# Kajtu_-DSP_processor.net
KiCad netlist of a schematic drawn in Altium Designer
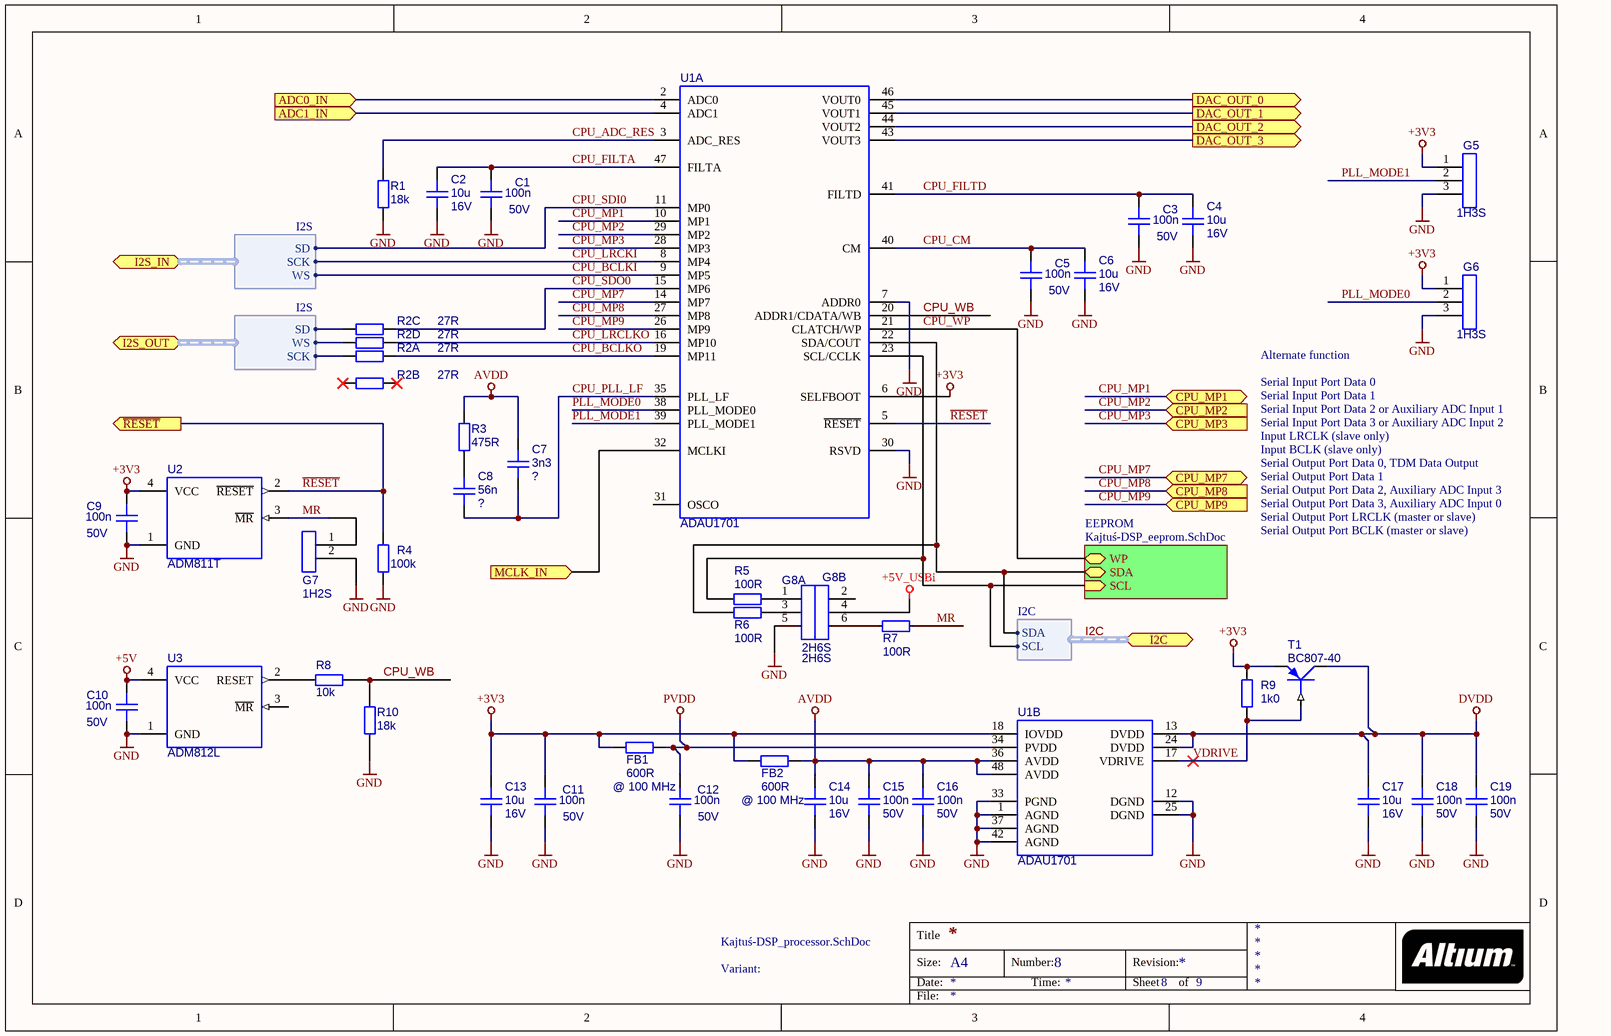
[diagram p0: Kajtuś-DSP_processor.SchDoc]

(export (version "E")
  (design (tool "Eeschema 10.0.6"))
  (components
    (comp (ref "C1")
      (value "100n")
      (footprint "C_0603_MA")
      (description "Kondensator ceramiczny SMD")
      (fields (field (name "PART NUMBER") "C_0603_100n_50V_X7R") (field (name "VOLTAGE") "50V"))
      (libsource (lib "AD_ostry_intlib") (part "C_0603_100n_50V_X7R"))
    )
    (comp (ref "C2")
      (value "10u")
      (footprint "C_0805_MA")
      (description "Kondensator ceramiczny SMD")
      (fields (field (name "PART NUMBER") "C_0805_10u_16V_X5R") (field (name "VOLTAGE") "16V"))
      (libsource (lib "AD_ostry_intlib") (part "C_0805_10u_16V_X5R"))
    )
    (comp (ref "C3")
      (value "100n")
      (footprint "C_0603_MA")
      (description "Kondensator ceramiczny SMD")
      (fields (field (name "PART NUMBER") "C_0603_100n_50V_X7R") (field (name "VOLTAGE") "50V"))
      (libsource (lib "AD_ostry_intlib") (part "C_0603_100n_50V_X7R"))
    )
    (comp (ref "C4")
      (value "10u")
      (footprint "C_0805_MA")
      (description "Kondensator ceramiczny SMD")
      (fields (field (name "PART NUMBER") "C_0805_10u_16V_X5R") (field (name "VOLTAGE") "16V"))
      (libsource (lib "AD_ostry_intlib") (part "C_0805_10u_16V_X5R"))
    )
    (comp (ref "C5")
      (value "100n")
      (footprint "C_0603_MA")
      (description "Kondensator ceramiczny SMD")
      (fields (field (name "PART NUMBER") "C_0603_100n_50V_X7R") (field (name "VOLTAGE") "50V"))
      (libsource (lib "AD_ostry_intlib") (part "C_0603_100n_50V_X7R"))
    )
    (comp (ref "C6")
      (value "10u")
      (footprint "C_0805_MA")
      (description "Kondensator ceramiczny SMD")
      (fields (field (name "PART NUMBER") "C_0805_10u_16V_X5R") (field (name "VOLTAGE") "16V"))
      (libsource (lib "AD_ostry_intlib") (part "C_0805_10u_16V_X5R"))
    )
    (comp (ref "C7")
      (value "3n3")
      (footprint "C_0603_MA")
      (description "Kondensator ceramiczny SMD")
      (fields (field (name "PART NUMBER") "C_SMD_MLCC_generic") (field (name "VOLTAGE") "?"))
      (libsource (lib "AD_ostry_intlib") (part "C_SMD_MLCC_generic"))
    )
    (comp (ref "C8")
      (value "56n")
      (footprint "C_0603_MA")
      (description "Kondensator ceramiczny SMD")
      (fields (field (name "PART NUMBER") "C_SMD_MLCC_generic") (field (name "VOLTAGE") "?"))
      (libsource (lib "AD_ostry_intlib") (part "C_SMD_MLCC_generic"))
    )
    (comp (ref "C9")
      (value "100n")
      (footprint "C_0603_MA")
      (description "Kondensator ceramiczny SMD")
      (fields (field (name "PART NUMBER") "C_0603_100n_50V_X7R") (field (name "VOLTAGE") "50V"))
      (libsource (lib "AD_ostry_intlib") (part "C_0603_100n_50V_X7R"))
    )
    (comp (ref "C10")
      (value "100n")
      (footprint "C_0603_MA")
      (description "Kondensator ceramiczny SMD")
      (fields (field (name "PART NUMBER") "C_0603_100n_50V_X7R") (field (name "VOLTAGE") "50V"))
      (libsource (lib "AD_ostry_intlib") (part "C_0603_100n_50V_X7R"))
    )
    (comp (ref "C11")
      (value "100n")
      (footprint "C_0603_MA")
      (description "Kondensator ceramiczny SMD")
      (fields (field (name "PART NUMBER") "C_0603_100n_50V_X7R") (field (name "VOLTAGE") "50V"))
      (libsource (lib "AD_ostry_intlib") (part "C_0603_100n_50V_X7R"))
    )
    (comp (ref "C12")
      (value "100n")
      (footprint "C_0603_MA")
      (description "Kondensator ceramiczny SMD")
      (fields (field (name "PART NUMBER") "C_0603_100n_50V_X7R") (field (name "VOLTAGE") "50V"))
      (libsource (lib "AD_ostry_intlib") (part "C_0603_100n_50V_X7R"))
    )
    (comp (ref "C13")
      (value "10u")
      (footprint "C_0805_MA")
      (description "Kondensator ceramiczny SMD")
      (fields (field (name "PART NUMBER") "C_0805_10u_16V_X5R") (field (name "VOLTAGE") "16V"))
      (libsource (lib "AD_ostry_intlib") (part "C_0805_10u_16V_X5R"))
    )
    (comp (ref "C14")
      (value "10u")
      (footprint "C_0805_MA")
      (description "Kondensator ceramiczny SMD")
      (fields (field (name "PART NUMBER") "C_0805_10u_16V_X5R") (field (name "VOLTAGE") "16V"))
      (libsource (lib "AD_ostry_intlib") (part "C_0805_10u_16V_X5R"))
    )
    (comp (ref "C15")
      (value "100n")
      (footprint "C_0603_MA")
      (description "Kondensator ceramiczny SMD")
      (fields (field (name "PART NUMBER") "C_0603_100n_50V_X7R") (field (name "VOLTAGE") "50V"))
      (libsource (lib "AD_ostry_intlib") (part "C_0603_100n_50V_X7R"))
    )
    (comp (ref "C16")
      (value "100n")
      (footprint "C_0603_MA")
      (description "Kondensator ceramiczny SMD")
      (fields (field (name "PART NUMBER") "C_0603_100n_50V_X7R") (field (name "VOLTAGE") "50V"))
      (libsource (lib "AD_ostry_intlib") (part "C_0603_100n_50V_X7R"))
    )
    (comp (ref "C17")
      (value "10u")
      (footprint "C_0805_MA")
      (description "Kondensator ceramiczny SMD")
      (fields (field (name "PART NUMBER") "C_0805_10u_16V_X5R") (field (name "VOLTAGE") "16V"))
      (libsource (lib "AD_ostry_intlib") (part "C_0805_10u_16V_X5R"))
    )
    (comp (ref "C18")
      (value "100n")
      (footprint "C_0603_MA")
      (description "Kondensator ceramiczny SMD")
      (fields (field (name "PART NUMBER") "C_0603_100n_50V_X7R") (field (name "VOLTAGE") "50V"))
      (libsource (lib "AD_ostry_intlib") (part "C_0603_100n_50V_X7R"))
    )
    (comp (ref "C19")
      (value "100n")
      (footprint "C_0603_MA")
      (description "Kondensator ceramiczny SMD")
      (fields (field (name "PART NUMBER") "C_0603_100n_50V_X7R") (field (name "VOLTAGE") "50V"))
      (libsource (lib "AD_ostry_intlib") (part "C_0603_100n_50V_X7R"))
    )
    (comp (ref "FB1")
      (value "600R")
      (footprint "R_0603_MA")
      (description "Koralik ferrytowy")
      (fields
        (field (name "MANUFACTURER") "Yageo")
        (field (name "PART NUMBER") "FB_0603_PBY160808T-601Y_600R_1A")
        (field (name "@ FREQUENCY") "@ 100 MHz")
      )
      (libsource (lib "AD_ostry_intlib") (part "FB_0603_PBY160808T-601Y_600R_1A"))
    )
    (comp (ref "FB2")
      (value "600R")
      (footprint "R_0603_MA")
      (description "Koralik ferrytowy")
      (fields
        (field (name "MANUFACTURER") "Yageo")
        (field (name "PART NUMBER") "FB_0603_PBY160808T-601Y_600R_1A")
        (field (name "@ FREQUENCY") "@ 100 MHz")
      )
      (libsource (lib "AD_ostry_intlib") (part "FB_0603_PBY160808T-601Y_600R_1A"))
    )
    (comp (ref "G5")
      (value "1H3S")
      (footprint "1H3S_FHS")
      (description "Listwa jednorzędowa, 1x3 piny, raster 2,54mm")
      (fields (field (name "PART NUMBER") "G_1H3S") (field (name "MANUFACTURER") "generic"))
      (libsource (lib "AD_ostry_intlib") (part "G_1H3S"))
    )
    (comp (ref "G6")
      (value "1H3S")
      (footprint "1H3S_FHS")
      (description "Listwa jednorzędowa, 1x3 piny, raster 2,54mm")
      (fields (field (name "PART NUMBER") "G_1H3S") (field (name "MANUFACTURER") "generic"))
      (libsource (lib "AD_ostry_intlib") (part "G_1H3S"))
    )
    (comp (ref "G7")
      (value "1H2S")
      (footprint "1H2S_FHS")
      (description "Listwa jednorzędowa, 1x2 piny, raster 2,54mm")
      (fields (field (name "PART NUMBER") "G_1H2S") (field (name "MANUFACTURER") "generic"))
      (libsource (lib "AD_ostry_intlib") (part "G_1H2S"))
    )
    (comp (ref "G8")
      (value "2H6S")
      (footprint "2H6S")
      (description "Listwa kołkowa")
      (fields (field (name "PART NUMBER") "G_2H6S") (field (name "MANUFACTURER") "Ninigi"))
      (libsource (lib "") (part "G_2H6S_1"))
    )
    (comp (ref "R1")
      (value "18k")
      (footprint "R_1206_MA")
      (description "SMD resistor")
      (fields (field (name "PART NUMBER") "?"))
      (libsource (lib "AD_ostry_intlib") (part "R_SMD_generic"))
    )
    (comp (ref "R2")
      (value "27R")
      (footprint "RA_1206")
      (description "SMD Resistor Array, 1206, 4x27R, 5%, 62.5mW")
      (fields (field (name "TOLERANCE") "5%"))
      (libsource (lib "AD_ostry_intlib") (part "RA_1206_4x27R_5%"))
    )
    (comp (ref "R3")
      (value "475R")
      (footprint "R_0603_MA")
      (description "SMD resistor")
      (fields (field (name "PART NUMBER") "?"))
      (libsource (lib "AD_ostry_intlib") (part "R_SMD_generic"))
    )
    (comp (ref "R4")
      (value "100k")
      (footprint "R_0603_MA")
      (description "Rezystor SMD")
      (fields (field (name "MANUFACTURER") "Royal Ohm") (field (name "PART NUMBER") "R_0603_100k_5%"))
      (libsource (lib "AD_ostry_intlib") (part "R_0603_100k_5%"))
    )
    (comp (ref "R5")
      (value "100R")
      (footprint "R_0603_MA")
      (description "Rezystor SMD")
      (fields (field (name "PART NUMBER") "R_0603_100R_5%") (field (name "MANUFACTURER") "Royal Ohm"))
      (libsource (lib "AD_ostry_intlib") (part "R_0603_100R_5%"))
    )
    (comp (ref "R6")
      (value "100R")
      (footprint "R_0603_MA")
      (description "Rezystor SMD")
      (fields (field (name "PART NUMBER") "R_0603_100R_5%") (field (name "MANUFACTURER") "Royal Ohm"))
      (libsource (lib "AD_ostry_intlib") (part "R_0603_100R_5%"))
    )
    (comp (ref "R7")
      (value "100R")
      (footprint "R_0603_MA")
      (description "Rezystor SMD")
      (fields (field (name "PART NUMBER") "R_0603_100R_5%") (field (name "MANUFACTURER") "Royal Ohm"))
      (libsource (lib "AD_ostry_intlib") (part "R_0603_100R_5%"))
    )
    (comp (ref "R8")
      (value "10k")
      (footprint "R_0603_MA")
      (description "Rezystor SMD")
      (fields (field (name "MANUFACTURER") "Royal Ohm") (field (name "PART NUMBER") "R_0603_10k_5%"))
      (libsource (lib "AD_ostry_intlib") (part "R_0603_10k_5%"))
    )
    (comp (ref "R9")
      (value "1k0")
      (footprint "R_0603_MA")
      (description "Rezystor SMD")
      (fields (field (name "MANUFACTURER") "Royal Ohm") (field (name "PART NUMBER") "R_0603_1k0_5%"))
      (libsource (lib "AD_ostry_intlib") (part "R_0603_1k0_5%"))
    )
    (comp (ref "R10")
      (value "18k")
      (footprint "R_0603_MA")
      (description "SMD resistor")
      (fields (field (name "PART NUMBER") "?"))
      (libsource (lib "AD_ostry_intlib") (part "R_SMD_generic"))
    )
    (comp (ref "T1")
      (value "BC807-40")
      (footprint "SOT-23")
      (description "Tranzystor bipolarny PNP")
      (fields (field (name "PART NUMBER") "T_SOT-23_BC807-40") (field (name "MANUFACTURER") "NXP"))
      (libsource (lib "AD_ostry_intlib") (part "T_SOT-23_BC807-40"))
    )
    (comp (ref "U1")
      (value "ADAU1701")
      (footprint "TSQFP50P900X900X160-48N")
      (description "SigmaDSP 28-/56-Bit Audio Processor with Two ADCs and Four DACs")
      (fields (field (name "MANUFACTURER") "Analog Devices"))
      (libsource (lib "AD_ostry_intlib") (part "U_ADAU1701"))
    )
    (comp (ref "U2")
      (value "ADM811T")
      (footprint "SOT-143")
      (description "Microprocessor Supervisory Circuit in 4-Lead SOT-143 with DSP")
      (fields (field (name "MANUFACTURER") "Analog Devices"))
      (libsource (lib "AD_ostry_intlib") (part "U_ADM811T"))
    )
    (comp (ref "U3")
      (value "ADM812L")
      (footprint "SOT-143")
      (description "Microprocessor Supervisory Circuit in 4-Lead SOT-143 with DSP")
      (fields (field (name "MANUFACTURER") "Analog Devices"))
      (libsource (lib "AD_ostry_intlib") (part "U_ADM812L"))
    )
  )
  (nets
    (net (code "3") (name "+3V3") (class "Default")
      (node (ref "C11") (pin "1") (pinfunction "1_1") (pintype "passive"))
      (node (ref "C13") (pin "1") (pinfunction "1_1") (pintype "passive"))
      (node (ref "C9") (pin "1") (pinfunction "1_1") (pintype "passive"))
      (node (ref "FB1") (pin "1") (pinfunction "1_1") (pintype "passive"))
      (node (ref "FB2") (pin "1") (pinfunction "1_1") (pintype "passive"))
      (node (ref "G5") (pin "1") (pinfunction "1_1") (pintype "passive"))
      (node (ref "G6") (pin "1") (pinfunction "1_1") (pintype "passive"))
      (node (ref "R9") (pin "1") (pinfunction "1_1") (pintype "passive"))
      (node (ref "T1") (pin "2") (pinfunction "E_2") (pintype "passive"))
      (node (ref "U1") (pin "18") (pinfunction "IOVDD_18") (pintype "passive"))
      (node (ref "U1") (pin "6") (pinfunction "SELFBOOT_6") (pintype "passive"))
      (node (ref "U2") (pin "4") (pinfunction "VCC_4") (pintype "power_in"))
    )
    (net (code "4") (name "+5V") (class "Default")
      (node (ref "C10") (pin "1") (pinfunction "1_1") (pintype "passive"))
      (node (ref "U3") (pin "4") (pinfunction "VCC_4") (pintype "power_in"))
    )
    (net (code "5") (name "+5V_USBi") (class "Default")
      (node (ref "G8") (pin "4") (pinfunction "4_4") (pintype "passive"))
    )
    (net (code "6") (name "/ADC0_IN") (class "Default")
      (node (ref "U1") (pin "2") (pinfunction "ADC0_2") (pintype "passive"))
    )
    (net (code "7") (name "/ADC1_IN") (class "Default")
      (node (ref "U1") (pin "4") (pinfunction "ADC1_4") (pintype "passive"))
    )
    (net (code "8") (name "/CPU_ADC_RES") (class "Default")
      (node (ref "R1") (pin "1") (pinfunction "1_1") (pintype "passive"))
      (node (ref "U1") (pin "3") (pinfunction "ADC_RES_3") (pintype "passive"))
    )
    (net (code "9") (name "/CPU_BCLKI") (class "Default")
      (node (ref "U1") (pin "9") (pinfunction "MP5_9") (pintype "passive"))
    )
    (net (code "10") (name "/CPU_BCLKO") (class "Default")
      (node (ref "R2") (pin "5") (pinfunction "5_5") (pintype "passive"))
      (node (ref "U1") (pin "19") (pinfunction "MP11_19") (pintype "passive"))
    )
    (net (code "11") (name "/CPU_CM") (class "Default")
      (node (ref "C5") (pin "1") (pinfunction "1_1") (pintype "passive"))
      (node (ref "C6") (pin "1") (pinfunction "1_1") (pintype "passive"))
      (node (ref "U1") (pin "40") (pinfunction "CM_40") (pintype "passive"))
    )
    (net (code "12") (name "/CPU_FILTA") (class "Default")
      (node (ref "C1") (pin "1") (pinfunction "1_1") (pintype "passive"))
      (node (ref "C2") (pin "1") (pinfunction "1_1") (pintype "passive"))
      (node (ref "U1") (pin "47") (pinfunction "FILTA_47") (pintype "passive"))
    )
    (net (code "13") (name "/CPU_FILTD") (class "Default")
      (node (ref "C3") (pin "1") (pinfunction "1_1") (pintype "passive"))
      (node (ref "C4") (pin "1") (pinfunction "1_1") (pintype "passive"))
      (node (ref "U1") (pin "41") (pinfunction "FILTD_41") (pintype "passive"))
    )
    (net (code "14") (name "/CPU_LRCKI") (class "Default")
      (node (ref "U1") (pin "8") (pinfunction "MP4_8") (pintype "passive"))
    )
    (net (code "15") (name "/CPU_LRCLKO") (class "Default")
      (node (ref "R2") (pin "8") (pinfunction "8_8") (pintype "passive"))
      (node (ref "U1") (pin "16") (pinfunction "MP10_16") (pintype "passive"))
    )
    (net (code "16") (name "/CPU_MP1") (class "Default")
      (node (ref "U1") (pin "10") (pinfunction "MP1_10") (pintype "passive"))
    )
    (net (code "17") (name "/CPU_MP2") (class "Default")
      (node (ref "U1") (pin "29") (pinfunction "MP2_29") (pintype "passive"))
    )
    (net (code "18") (name "/CPU_MP3") (class "Default")
      (node (ref "U1") (pin "28") (pinfunction "MP3_28") (pintype "passive"))
    )
    (net (code "19") (name "/CPU_MP7") (class "Default")
      (node (ref "U1") (pin "14") (pinfunction "MP7_14") (pintype "passive"))
    )
    (net (code "20") (name "/CPU_MP8") (class "Default")
      (node (ref "U1") (pin "27") (pinfunction "MP8_27") (pintype "passive"))
    )
    (net (code "21") (name "/CPU_MP9") (class "Default")
      (node (ref "U1") (pin "26") (pinfunction "MP9_26") (pintype "passive"))
    )
    (net (code "22") (name "/CPU_PLL_LF") (class "Default")
      (node (ref "C7") (pin "2") (pinfunction "2_2") (pintype "passive"))
      (node (ref "C8") (pin "2") (pinfunction "2_2") (pintype "passive"))
      (node (ref "U1") (pin "35") (pinfunction "PLL_LF_35") (pintype "passive"))
    )
    (net (code "23") (name "/CPU_SDI0") (class "Default")
      (node (ref "U1") (pin "11") (pinfunction "MP0_11") (pintype "passive"))
    )
    (net (code "24") (name "/CPU_SDO0") (class "Default")
      (node (ref "R2") (pin "7") (pinfunction "7_7") (pintype "passive"))
      (node (ref "U1") (pin "15") (pinfunction "MP6_15") (pintype "passive"))
    )
    (net (code "25") (name "/CPU_WB") (class "Default")
      (node (ref "R10") (pin "1") (pinfunction "1_1") (pintype "passive"))
      (node (ref "R8") (pin "2") (pinfunction "2_2") (pintype "passive"))
      (node (ref "U1") (pin "20") (pinfunction "ADDR1/CDATA/WB_20") (pintype "passive"))
    )
    (net (code "26") (name "/CPU_WP") (class "Default")
      (node (ref "U1") (pin "21") (pinfunction "CLATCH/WP_21") (pintype "passive"))
    )
    (net (code "27") (name "/DAC_OUT_0") (class "Default")
      (node (ref "U1") (pin "46") (pinfunction "VOUT0_46") (pintype "passive"))
    )
    (net (code "28") (name "/DAC_OUT_1") (class "Default")
      (node (ref "U1") (pin "45") (pinfunction "VOUT1_45") (pintype "passive"))
    )
    (net (code "29") (name "/DAC_OUT_2") (class "Default")
      (node (ref "U1") (pin "44") (pinfunction "VOUT2_44") (pintype "passive"))
    )
    (net (code "30") (name "/DAC_OUT_3") (class "Default")
      (node (ref "U1") (pin "43") (pinfunction "VOUT3_43") (pintype "passive"))
    )
    (net (code "32") (name "/MCLK_IN") (class "Default")
      (node (ref "U1") (pin "32") (pinfunction "MCLKI_32") (pintype "passive"))
    )
    (net (code "33") (name "/MR") (class "Default")
      (node (ref "G7") (pin "1") (pinfunction "1_1") (pintype "passive"))
      (node (ref "R7") (pin "2") (pinfunction "2_2") (pintype "passive"))
      (node (ref "U2") (pin "3") (pinfunction "~{MR}_3") (pintype "input"))
    )
    (net (code "34") (name "/PLL_MODE0") (class "Default")
      (node (ref "G6") (pin "2") (pinfunction "2_2") (pintype "passive"))
      (node (ref "U1") (pin "38") (pinfunction "PLL_MODE0_38") (pintype "passive"))
    )
    (net (code "35") (name "/PLL_MODE1") (class "Default")
      (node (ref "G5") (pin "2") (pinfunction "2_2") (pintype "passive"))
      (node (ref "U1") (pin "39") (pinfunction "PLL_MODE1_39") (pintype "passive"))
    )
    (net (code "36") (name "/SCL") (class "Default")
      (node (ref "R5") (pin "1") (pinfunction "1_1") (pintype "passive"))
      (node (ref "U1") (pin "23") (pinfunction "SCL/CCLK_23") (pintype "passive"))
    )
    (net (code "37") (name "/SDA") (class "Default")
      (node (ref "R6") (pin "1") (pinfunction "1_1") (pintype "passive"))
      (node (ref "U1") (pin "22") (pinfunction "SDA/COUT_22") (pintype "passive"))
    )
    (net (code "40") (name "/VDRIVE") (class "Default")
      (node (ref "R9") (pin "2") (pinfunction "2_2") (pintype "passive"))
      (node (ref "T1") (pin "1") (pinfunction "B_1") (pintype "input"))
      (node (ref "U1") (pin "17") (pinfunction "VDRIVE_17") (pintype "passive"))
    )
    (net (code "41") (name "/~{RESET}") (class "Default")
      (node (ref "R4") (pin "1") (pinfunction "1_1") (pintype "passive"))
      (node (ref "U1") (pin "5") (pinfunction "~{RESET}_5") (pintype "passive"))
      (node (ref "U2") (pin "2") (pinfunction "~{RESET}_2") (pintype "output"))
    )
    (net (code "42") (name "AVDD") (class "Default")
      (node (ref "C14") (pin "1") (pinfunction "1_1") (pintype "passive"))
      (node (ref "C15") (pin "1") (pinfunction "1_1") (pintype "passive"))
      (node (ref "C16") (pin "1") (pinfunction "1_1") (pintype "passive"))
      (node (ref "C7") (pin "1") (pinfunction "1_1") (pintype "passive"))
      (node (ref "FB2") (pin "2") (pinfunction "2_2") (pintype "passive"))
      (node (ref "R3") (pin "1") (pinfunction "1_1") (pintype "passive"))
      (node (ref "U1") (pin "36") (pinfunction "AVDD_36") (pintype "passive"))
      (node (ref "U1") (pin "48") (pinfunction "AVDD_48") (pintype "passive"))
    )
    (net (code "43") (name "DVDD") (class "Default")
      (node (ref "C17") (pin "1") (pinfunction "1_1") (pintype "passive"))
      (node (ref "C18") (pin "1") (pinfunction "1_1") (pintype "passive"))
      (node (ref "C19") (pin "1") (pinfunction "1_1") (pintype "passive"))
      (node (ref "T1") (pin "3") (pinfunction "C_3") (pintype "passive"))
      (node (ref "U1") (pin "13") (pinfunction "DVDD_13") (pintype "passive"))
      (node (ref "U1") (pin "24") (pinfunction "DVDD_24") (pintype "passive"))
    )
    (net (code "44") (name "GND") (class "Default")
      (node (ref "C1") (pin "2") (pinfunction "2_2") (pintype "passive"))
      (node (ref "C10") (pin "2") (pinfunction "2_2") (pintype "passive"))
      (node (ref "C11") (pin "2") (pinfunction "2_2") (pintype "passive"))
      (node (ref "C12") (pin "2") (pinfunction "2_2") (pintype "passive"))
      (node (ref "C13") (pin "2") (pinfunction "2_2") (pintype "passive"))
      (node (ref "C14") (pin "2") (pinfunction "2_2") (pintype "passive"))
      (node (ref "C15") (pin "2") (pinfunction "2_2") (pintype "passive"))
      (node (ref "C16") (pin "2") (pinfunction "2_2") (pintype "passive"))
      (node (ref "C17") (pin "2") (pinfunction "2_2") (pintype "passive"))
      (node (ref "C18") (pin "2") (pinfunction "2_2") (pintype "passive"))
      (node (ref "C19") (pin "2") (pinfunction "2_2") (pintype "passive"))
      (node (ref "C2") (pin "2") (pinfunction "2_2") (pintype "passive"))
      (node (ref "C3") (pin "2") (pinfunction "2_2") (pintype "passive"))
      (node (ref "C4") (pin "2") (pinfunction "2_2") (pintype "passive"))
      (node (ref "C5") (pin "2") (pinfunction "2_2") (pintype "passive"))
      (node (ref "C6") (pin "2") (pinfunction "2_2") (pintype "passive"))
      (node (ref "C9") (pin "2") (pinfunction "2_2") (pintype "passive"))
      (node (ref "G5") (pin "3") (pinfunction "3_3") (pintype "passive"))
      (node (ref "G6") (pin "3") (pinfunction "3_3") (pintype "passive"))
      (node (ref "G7") (pin "2") (pinfunction "2_2") (pintype "passive"))
      (node (ref "G8") (pin "5") (pinfunction "5_5") (pintype "passive"))
      (node (ref "R1") (pin "2") (pinfunction "2_2") (pintype "passive"))
      (node (ref "R10") (pin "2") (pinfunction "2_2") (pintype "passive"))
      (node (ref "R4") (pin "2") (pinfunction "2_2") (pintype "passive"))
      (node (ref "U1") (pin "1") (pinfunction "AGND_1") (pintype "passive"))
      (node (ref "U1") (pin "12") (pinfunction "DGND_12") (pintype "passive"))
      (node (ref "U1") (pin "25") (pinfunction "DGND_25") (pintype "passive"))
      (node (ref "U1") (pin "30") (pinfunction "RSVD_30") (pintype "passive"))
      (node (ref "U1") (pin "33") (pinfunction "PGND_33") (pintype "passive"))
      (node (ref "U1") (pin "37") (pinfunction "AGND_37") (pintype "passive"))
      (node (ref "U1") (pin "42") (pinfunction "AGND_42") (pintype "passive"))
      (node (ref "U1") (pin "7") (pinfunction "ADDR0_7") (pintype "passive"))
      (node (ref "U2") (pin "1") (pinfunction "GND_1") (pintype "power_in"))
      (node (ref "U3") (pin "1") (pinfunction "GND_1") (pintype "power_in"))
    )
    (net (code "45") (name "Net-(C8-Pad1)") (class "Default")
      (node (ref "C8") (pin "1") (pinfunction "1_1") (pintype "passive"))
      (node (ref "R3") (pin "2") (pinfunction "2_2") (pintype "passive"))
    )
    (net (code "46") (name "Net-(G8-Pad1)") (class "Default")
      (node (ref "G8") (pin "1") (pinfunction "1_1") (pintype "passive"))
      (node (ref "R5") (pin "2") (pinfunction "2_2") (pintype "passive"))
    )
    (net (code "47") (name "Net-(G8-Pad3)") (class "Default")
      (node (ref "G8") (pin "3") (pinfunction "3_3") (pintype "passive"))
      (node (ref "R6") (pin "2") (pinfunction "2_2") (pintype "passive"))
    )
    (net (code "48") (name "Net-(G8-Pad6)") (class "Default")
      (node (ref "G8") (pin "6") (pinfunction "6_6") (pintype "passive"))
      (node (ref "R7") (pin "1") (pinfunction "1_1") (pintype "passive"))
    )
    (net (code "49") (name "Net-(U3-RESET)") (class "Default")
      (node (ref "R8") (pin "1") (pinfunction "1_1") (pintype "passive"))
      (node (ref "U3") (pin "2") (pinfunction "RESET_2") (pintype "output"))
    )
    (net (code "50") (name "PVDD") (class "Default")
      (node (ref "C12") (pin "1") (pinfunction "1_1") (pintype "passive"))
      (node (ref "FB1") (pin "2") (pinfunction "2_2") (pintype "passive"))
      (node (ref "U1") (pin "34") (pinfunction "PVDD_34") (pintype "passive"))
    )
    (net (code "51") (name "unconnected-(G8-Pad2)") (class "Default")
      (node (ref "G8") (pin "2") (pinfunction "2_2") (pintype "passive"))
    )
    (net (code "52") (name "unconnected-(R2-Pad1)") (class "Default")
      (node (ref "R2") (pin "1") (pinfunction "1_1") (pintype "passive"))
    )
    (net (code "53") (name "unconnected-(R2-Pad2)") (class "Default")
      (node (ref "R2") (pin "2") (pinfunction "2_2") (pintype "passive+no_connect"))
    )
    (net (code "54") (name "unconnected-(R2-Pad3)") (class "Default")
      (node (ref "R2") (pin "3") (pinfunction "3_3") (pintype "passive"))
    )
    (net (code "55") (name "unconnected-(R2-Pad4)") (class "Default")
      (node (ref "R2") (pin "4") (pinfunction "4_4") (pintype "passive"))
    )
    (net (code "56") (name "unconnected-(R2-Pad6)") (class "Default")
      (node (ref "R2") (pin "6") (pinfunction "6_6") (pintype "passive+no_connect"))
    )
    (net (code "57") (name "unconnected-(U1A-OSCO-Pad31)") (class "Default")
      (node (ref "U1") (pin "31") (pinfunction "OSCO_31") (pintype "passive"))
    )
    (net (code "58") (name "unconnected-(U3-~{MR}-Pad3)") (class "Default")
      (node (ref "U3") (pin "3") (pinfunction "~{MR}_3") (pintype "input"))
    )
  )
)
